# EMU_adc.net
KiCad netlist of a schematic drawn in Altium Designer
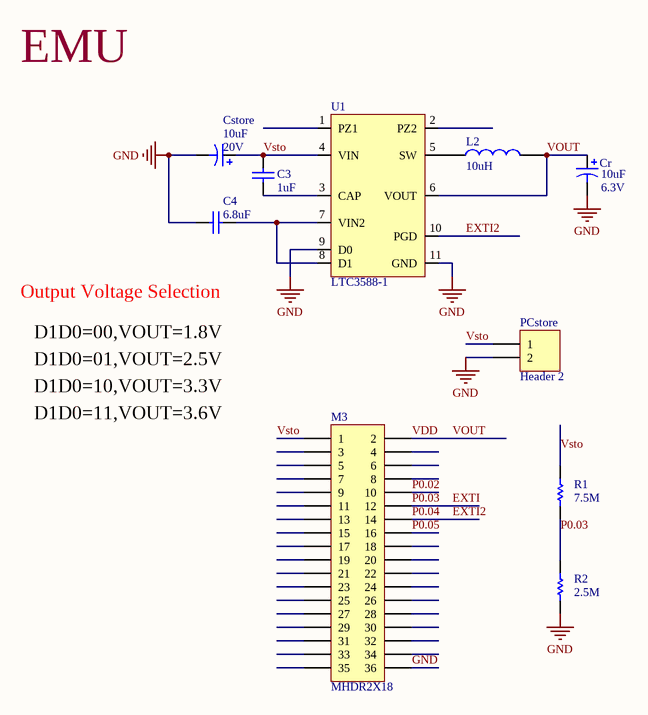
[diagram p0: EMU_adc.SchDoc]

(export (version "E")
  (design (tool "Eeschema 10.0.6"))
  (components
    (comp (ref "C3")
      (value "1uF")
      (footprint "6-0805_N")
      (description "Capacitor")
      (fields (field (name "Comment") "CAP") (field (name "PUBLISHER") "Altium Limited"))
      (libsource (lib "Harry_PCBLib") (part "Cap"))
    )
    (comp (ref "C4")
      (value "6.8uF")
      (footprint "6-0805_N")
      (description "Capacitor")
      (fields (field (name "Comment") "CAP") (field (name "PUBLISHER") "Altium Limited"))
      (libsource (lib "Harry_PCBLib") (part "Cap"))
    )
    (comp (ref "Cr")
      (value "6.3V")
      (footprint "3216[1206]")
      (description "Polarized Capacitor (Radial)")
      (fields (field (name "ALTIUM_VALUE") "10uF") (field (name "PUBLISHER") "Altium Limited"))
      (libsource (lib "Miscellaneous Devices") (part "Cap Pol1"))
    )
    (comp (ref "Cstore")
      (value "10uF")
      (footprint "钽电容")
      (description "Polarized Capacitor (Radial)")
      (fields
        (field (name "NOMINAL VOLTAGE") "20V")
        (field (name "Comment") "Cap Pol1")
        (field (name "PUBLISHER") "Altium Limited")
      )
      (libsource (lib "Miscellaneous Devices") (part "Cap Pol1"))
    )
    (comp (ref "L2") (value "10uH") (footprint "1812") (libsource (lib "Harry_PCBLib") (part "INDUCTOR")))
    (comp (ref "M3")
      (value "MHDR2X18")
      (footprint "header:module9x4")
      (description "Header, 18-Pin, Dual row")
      (fields (field (name "PUBLISHER") "Altium Limited"))
      (libsource (lib "Miscellaneous Connectors") (part "MHDR2X18"))
    )
    (comp (ref "PCstore")
      (value "Header 2")
      (footprint "HDR1X2")
      (description "Header, 2-Pin")
      (fields (field (name "PUBLISHER") "Altium Limited"))
      (libsource (lib "Miscellaneous Connectors") (part "Header 2"))
    )
    (comp (ref "R1")
      (value "7.5M")
      (footprint "6-0805_N")
      (description "Resistor")
      (fields (field (name "Comment") "Res1") (field (name "PUBLISHER") "Altium Limited"))
      (libsource (lib "Miscellaneous Devices") (part "Res1"))
    )
    (comp (ref "R2")
      (value "2.5M")
      (footprint "6-0805_N")
      (description "Resistor")
      (fields (field (name "Comment") "Res1") (field (name "PUBLISHER") "Altium Limited"))
      (libsource (lib "Miscellaneous Devices") (part "Res1"))
    )
    (comp (ref "U1")
      (value "LTC3588-1")
      (footprint "LTC 3588-1")
      (description "Nanopower energy harvesting power supply")
      (libsource (lib "Self-power SSHI") (part "LTC3588-1"))
    )
  )
  (nets
    (net (code "1") (name "/EXTI") (class "Default")
      (node (ref "M3") (pin "12") (pinfunction "12_12") (pintype "passive"))
      (node (ref "R1") (pin "1") (pinfunction "1_1") (pintype "passive"))
      (node (ref "R2") (pin "2") (pinfunction "2_2") (pintype "passive"))
    )
    (net (code "2") (name "/EXTI2") (class "Default")
      (node (ref "M3") (pin "14") (pinfunction "14_14") (pintype "passive"))
      (node (ref "U1") (pin "10") (pinfunction "PGD_10") (pintype "passive"))
    )
    (net (code "3") (name "/P0.02") (class "Default")
      (node (ref "M3") (pin "10") (pinfunction "10_10") (pintype "passive"))
    )
    (net (code "4") (name "/P0.05") (class "Default")
      (node (ref "M3") (pin "16") (pinfunction "16_16") (pintype "passive"))
    )
    (net (code "5") (name "/VDD") (class "Default")
      (node (ref "Cr") (pin "1") (pinfunction "1_1") (pintype "passive"))
      (node (ref "L2") (pin "2") (pinfunction "2_2") (pintype "passive"))
      (node (ref "M3") (pin "2") (pinfunction "2_2") (pintype "passive"))
      (node (ref "U1") (pin "6") (pinfunction "VOUT_6") (pintype "passive"))
    )
    (net (code "6") (name "/Vsto") (class "Default")
      (node (ref "C3") (pin "2") (pinfunction "2_2") (pintype "passive"))
      (node (ref "Cstore") (pin "1") (pinfunction "1_1") (pintype "passive"))
      (node (ref "M3") (pin "1") (pinfunction "1_1") (pintype "passive"))
      (node (ref "PCstore") (pin "1") (pinfunction "1_1") (pintype "passive"))
      (node (ref "R1") (pin "2") (pinfunction "2_2") (pintype "passive"))
      (node (ref "U1") (pin "4") (pinfunction "VIN_4") (pintype "passive"))
    )
    (net (code "7") (name "GND") (class "Default")
      (node (ref "C4") (pin "2") (pinfunction "2_2") (pintype "passive"))
      (node (ref "Cr") (pin "2") (pinfunction "2_2") (pintype "passive"))
      (node (ref "Cstore") (pin "2") (pinfunction "2_2") (pintype "passive"))
      (node (ref "M3") (pin "36") (pinfunction "36_36") (pintype "passive"))
      (node (ref "PCstore") (pin "2") (pinfunction "2_2") (pintype "passive"))
      (node (ref "R2") (pin "1") (pinfunction "1_1") (pintype "passive"))
      (node (ref "U1") (pin "11") (pinfunction "GND_11") (pintype "passive"))
      (node (ref "U1") (pin "9") (pinfunction "D0_9") (pintype "passive"))
    )
    (net (code "8") (name "Net-(U1-CAP)") (class "Default")
      (node (ref "C3") (pin "1") (pinfunction "1_1") (pintype "passive"))
      (node (ref "U1") (pin "3") (pinfunction "CAP_3") (pintype "passive"))
    )
    (net (code "9") (name "Net-(U1-D1)") (class "Default")
      (node (ref "C4") (pin "1") (pinfunction "1_1") (pintype "passive"))
      (node (ref "U1") (pin "7") (pinfunction "VIN2_7") (pintype "passive"))
      (node (ref "U1") (pin "8") (pinfunction "D1_8") (pintype "passive"))
    )
    (net (code "10") (name "Net-(U1-SW)") (class "Default")
      (node (ref "L2") (pin "1") (pinfunction "1_1") (pintype "passive"))
      (node (ref "U1") (pin "5") (pinfunction "SW_5") (pintype "passive"))
    )
    (net (code "11") (name "unconnected-(M3-Pad3)") (class "Default")
      (node (ref "M3") (pin "3") (pinfunction "3_3") (pintype "passive"))
    )
    (net (code "12") (name "unconnected-(M3-Pad4)") (class "Default")
      (node (ref "M3") (pin "4") (pinfunction "4_4") (pintype "passive"))
    )
    (net (code "13") (name "unconnected-(M3-Pad5)") (class "Default")
      (node (ref "M3") (pin "5") (pinfunction "5_5") (pintype "passive"))
    )
    (net (code "14") (name "unconnected-(M3-Pad6)") (class "Default")
      (node (ref "M3") (pin "6") (pinfunction "6_6") (pintype "passive"))
    )
    (net (code "15") (name "unconnected-(M3-Pad7)") (class "Default")
      (node (ref "M3") (pin "7") (pinfunction "7_7") (pintype "passive"))
    )
    (net (code "16") (name "unconnected-(M3-Pad8)") (class "Default")
      (node (ref "M3") (pin "8") (pinfunction "8_8") (pintype "passive"))
    )
    (net (code "17") (name "unconnected-(M3-Pad9)") (class "Default")
      (node (ref "M3") (pin "9") (pinfunction "9_9") (pintype "passive"))
    )
    (net (code "18") (name "unconnected-(M3-Pad11)") (class "Default")
      (node (ref "M3") (pin "11") (pinfunction "11_11") (pintype "passive"))
    )
    (net (code "19") (name "unconnected-(M3-Pad13)") (class "Default")
      (node (ref "M3") (pin "13") (pinfunction "13_13") (pintype "passive"))
    )
    (net (code "20") (name "unconnected-(M3-Pad15)") (class "Default")
      (node (ref "M3") (pin "15") (pinfunction "15_15") (pintype "passive"))
    )
    (net (code "21") (name "unconnected-(M3-Pad17)") (class "Default")
      (node (ref "M3") (pin "17") (pinfunction "17_17") (pintype "passive"))
    )
    (net (code "22") (name "unconnected-(M3-Pad18)") (class "Default")
      (node (ref "M3") (pin "18") (pinfunction "18_18") (pintype "passive"))
    )
    (net (code "23") (name "unconnected-(M3-Pad19)") (class "Default")
      (node (ref "M3") (pin "19") (pinfunction "19_19") (pintype "passive"))
    )
    (net (code "24") (name "unconnected-(M3-Pad20)") (class "Default")
      (node (ref "M3") (pin "20") (pinfunction "20_20") (pintype "passive"))
    )
    (net (code "25") (name "unconnected-(M3-Pad21)") (class "Default")
      (node (ref "M3") (pin "21") (pinfunction "21_21") (pintype "passive"))
    )
    (net (code "26") (name "unconnected-(M3-Pad22)") (class "Default")
      (node (ref "M3") (pin "22") (pinfunction "22_22") (pintype "passive"))
    )
    (net (code "27") (name "unconnected-(M3-Pad23)") (class "Default")
      (node (ref "M3") (pin "23") (pinfunction "23_23") (pintype "passive"))
    )
    (net (code "28") (name "unconnected-(M3-Pad24)") (class "Default")
      (node (ref "M3") (pin "24") (pinfunction "24_24") (pintype "passive"))
    )
    (net (code "29") (name "unconnected-(M3-Pad25)") (class "Default")
      (node (ref "M3") (pin "25") (pinfunction "25_25") (pintype "passive"))
    )
    (net (code "30") (name "unconnected-(M3-Pad26)") (class "Default")
      (node (ref "M3") (pin "26") (pinfunction "26_26") (pintype "passive"))
    )
    (net (code "31") (name "unconnected-(M3-Pad27)") (class "Default")
      (node (ref "M3") (pin "27") (pinfunction "27_27") (pintype "passive"))
    )
    (net (code "32") (name "unconnected-(M3-Pad28)") (class "Default")
      (node (ref "M3") (pin "28") (pinfunction "28_28") (pintype "passive"))
    )
    (net (code "33") (name "unconnected-(M3-Pad29)") (class "Default")
      (node (ref "M3") (pin "29") (pinfunction "29_29") (pintype "passive"))
    )
    (net (code "34") (name "unconnected-(M3-Pad30)") (class "Default")
      (node (ref "M3") (pin "30") (pinfunction "30_30") (pintype "passive"))
    )
    (net (code "35") (name "unconnected-(M3-Pad31)") (class "Default")
      (node (ref "M3") (pin "31") (pinfunction "31_31") (pintype "passive"))
    )
    (net (code "36") (name "unconnected-(M3-Pad32)") (class "Default")
      (node (ref "M3") (pin "32") (pinfunction "32_32") (pintype "passive"))
    )
    (net (code "37") (name "unconnected-(M3-Pad33)") (class "Default")
      (node (ref "M3") (pin "33") (pinfunction "33_33") (pintype "passive"))
    )
    (net (code "38") (name "unconnected-(M3-Pad34)") (class "Default")
      (node (ref "M3") (pin "34") (pinfunction "34_34") (pintype "passive"))
    )
    (net (code "39") (name "unconnected-(M3-Pad35)") (class "Default")
      (node (ref "M3") (pin "35") (pinfunction "35_35") (pintype "passive"))
    )
    (net (code "40") (name "unconnected-(U1-PZ1-Pad1)") (class "Default")
      (node (ref "U1") (pin "1") (pinfunction "PZ1_1") (pintype "passive"))
    )
    (net (code "41") (name "unconnected-(U1-PZ2-Pad2)") (class "Default")
      (node (ref "U1") (pin "2") (pinfunction "PZ2_2") (pintype "passive"))
    )
  )
)
